# power-vddr.net
KiCad netlist of a schematic drawn in Altium Designer
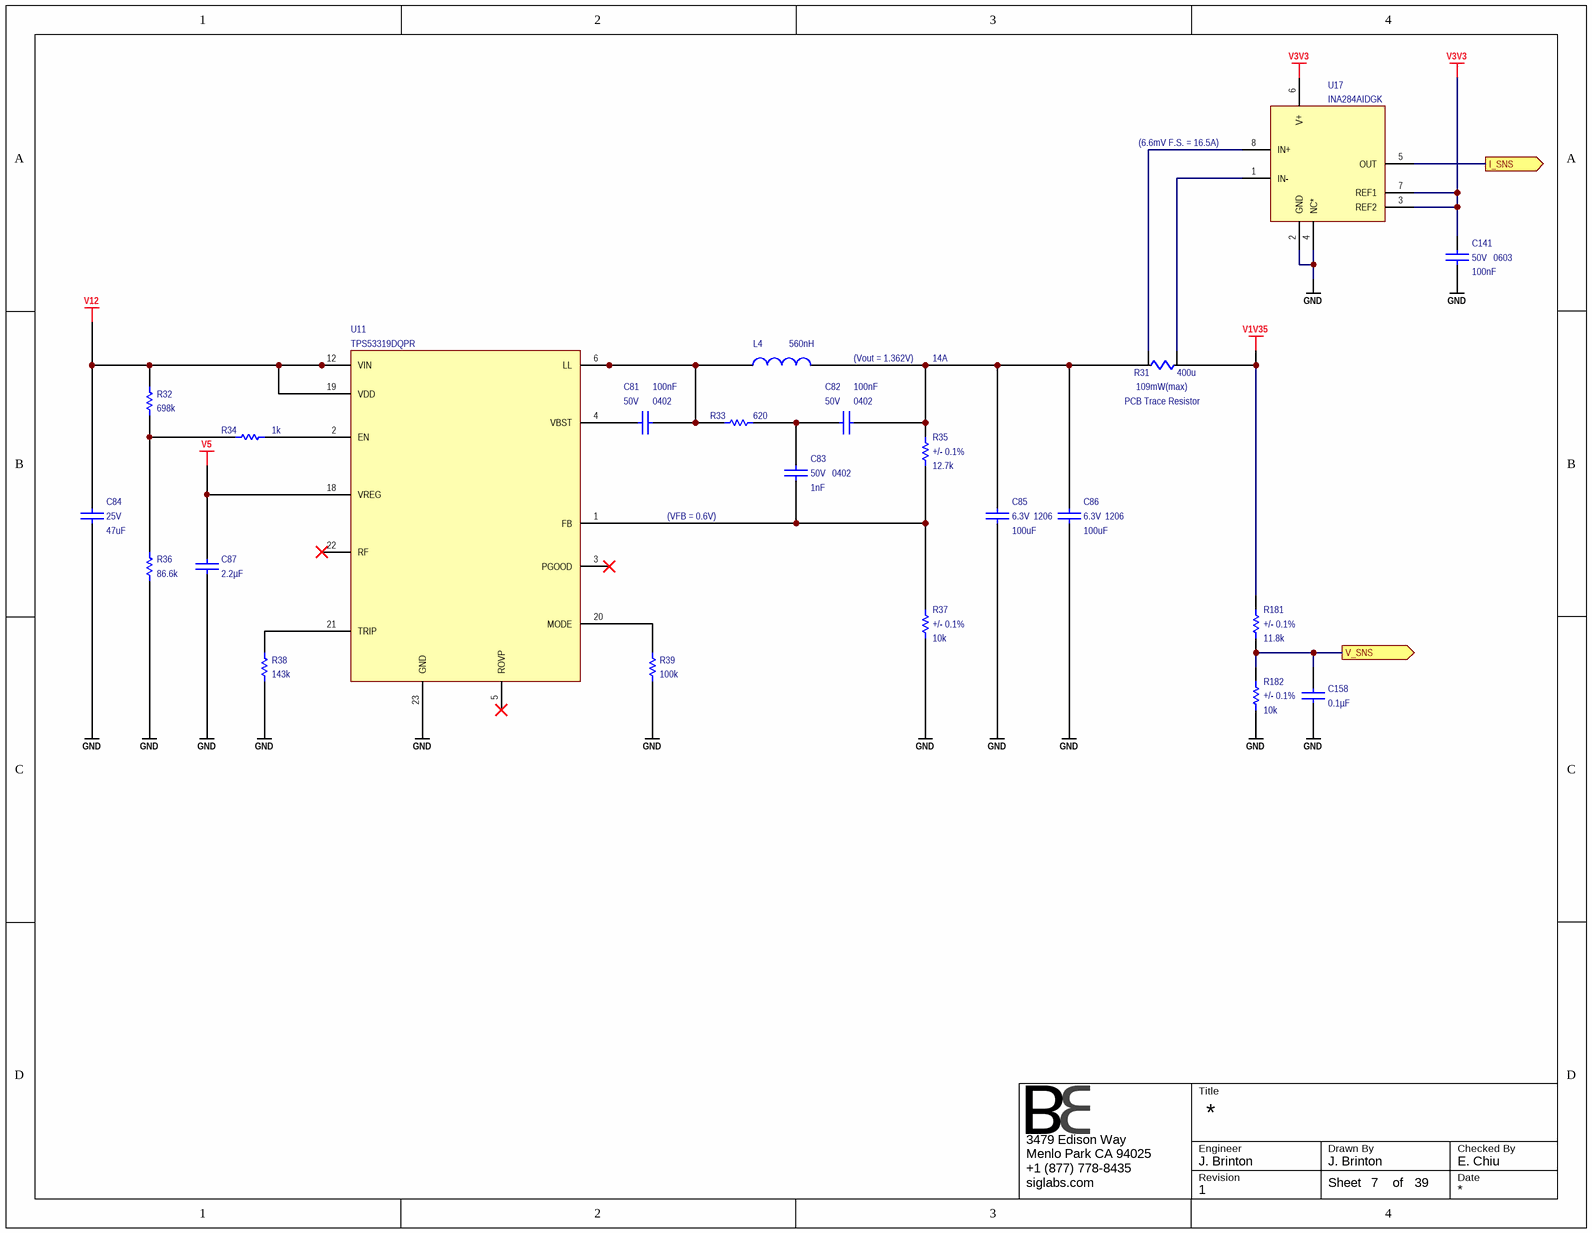
[diagram p0: power-vddr.SchDoc]

(export (version "E")
  (design (tool "Eeschema 10.0.6"))
  (components
    (comp (ref "C81")
      (value "100nF")
      (footprint "CAPC1005X55N")
      (description "Ceramic Capacitor 100nF +/-20% 50V X7R 0402")
      (fields
        (field (name "MANUFACTURER") "Murata Electronics")
        (field (name "VOLTAGE") "50V")
        (field (name "PCB PACKAGE") "0402")
        (field (name "Comment") "GRM155R71H104ME14D")
      )
      (libsource (lib "generic") (part "CAP 0402"))
    )
    (comp (ref "C82")
      (value "100nF")
      (footprint "CAPC1005X55N")
      (description "Ceramic Capacitor 100nF +/-20% 50V X7R 0402")
      (fields
        (field (name "MANUFACTURER") "Murata Electronics")
        (field (name "VOLTAGE") "50V")
        (field (name "PCB PACKAGE") "0402")
        (field (name "Comment") "GRM155R71H104ME14D")
      )
      (libsource (lib "generic") (part "CAP 0402"))
    )
    (comp (ref "C83")
      (value "1nF")
      (footprint "generic:CAPC1005X55N")
      (description "Ceramic Capacitor 1nF +/-10% 50V X7R 0402")
      (fields
        (field (name "MANUFACTURER") "Murata Electronics")
        (field (name "VOLTAGE") "50V")
        (field (name "PCB PACKAGE") "0402")
        (field (name "Comment") "GRM155R71H102KA01J")
      )
      (libsource (lib "generic") (part "CAP"))
    )
    (comp (ref "C84")
      (value "47uF")
      (footprint "tdk:CKG57N")
      (description "Stacked MLCC Capacitor 47uF +/-20% 25V SMD")
      (fields
        (field (name "MANUFACTURER") "TDK Corporation")
        (field (name "TOLERANCE") "+/-20%")
        (field (name "VOLTAGE") "25V")
      )
      (libsource (lib "") (part "CAP_1"))
    )
    (comp (ref "C85")
      (value "100uF")
      (footprint "generic:CAPC3216X180L55N")
      (description "Ceramic Capacitor 100uF +/-20% 6.3V X5R 1206")
      (fields
        (field (name "MANUFACTURER") "Murata Electronics")
        (field (name "VOLTAGE") "6.3V")
        (field (name "PCB PACKAGE") "1206")
        (field (name "Comment") "GRM31CR60J107ME39K")
      )
      (libsource (lib "generic") (part "CAP"))
    )
    (comp (ref "C86")
      (value "100uF")
      (footprint "generic:CAPC3216X180L55N")
      (description "Ceramic Capacitor 100uF +/-20% 6.3V X5R 1206")
      (fields
        (field (name "MANUFACTURER") "Murata Electronics")
        (field (name "VOLTAGE") "6.3V")
        (field (name "PCB PACKAGE") "1206")
        (field (name "Comment") "GRM31CR60J107ME39K")
      )
      (libsource (lib "generic") (part "CAP"))
    )
    (comp (ref "C87")
      (value "2.2µF")
      (footprint "CAPC1608X90N")
      (description "CAP CER 2.2UF 10V 10% X7R 0603")
      (fields (field (name "MANUFACTURER") "Murata Electronics") (field (name "TOLERANCE") "±10%"))
      (libsource (lib "murata") (part "GRM188R71A225KE15D"))
    )
    (comp (ref "C141")
      (value "100nF")
      (footprint "generic:CAPC1608X90N")
      (description "Ceramic Capacitor 100nF +/-10% 50V X7R 0603")
      (fields
        (field (name "MANUFACTURER") "Kemet")
        (field (name "VOLTAGE") "50V")
        (field (name "PCB PACKAGE") "0603")
        (field (name "Comment") "C0603C104K5RACTU")
      )
      (libsource (lib "generic") (part "CAP"))
    )
    (comp (ref "C158")
      (value "0.1µF")
      (footprint "CAPC1005X56N")
      (description "CAP CER 0.1UF 10V 10% X7R 0402")
      (fields (field (name "MANUFACTURER") "Murata Electronics") (field (name "TOLERANCE") "±10%"))
      (libsource (lib "murata") (part "GRM155R71A104KA01J"))
    )
    (comp (ref "L4")
      (value "560nH")
      (footprint "coilcraft:XAL6030")
      (description "Shielded Power Inductor 560nH, 17A")
      (fields (field (name "MANUFACTURER") "Coilcraft") (field (name "Comment") "XAL6030-561MEB"))
      (libsource (lib "generic") (part "INDUCTOR"))
    )
    (comp (ref "R31")
      (value "400u")
      (footprint "RES0.0004")
      (description "Current Sense Resistor 400uOhm TRACE")
      (fields (field (name "Comment") "RES0.0004"))
      (libsource (lib "copper_suicide") (part "RES0.0004"))
    )
    (comp (ref "R32")
      (value "698k")
      (footprint "RESC1005X40N")
      (description "Thick Film Resistor 698k +/-1% 0402")
      (fields (field (name "MANUFACTURER") "Panasonic") (field (name "Comment") "ERJ-2RKF6983X"))
      (libsource (lib "generic") (part "RES 0402"))
    )
    (comp (ref "R33")
      (value "620")
      (footprint "RESC1005X40N")
      (description "Thick Film Resistor 620 +/-5% 0402")
      (fields (field (name "MANUFACTURER") "Panasonic") (field (name "Comment") "ERJ-2GEJ621X"))
      (libsource (lib "generic") (part "RES 0402"))
    )
    (comp (ref "R34")
      (value "1k")
      (footprint "RESC1005X40N")
      (description "Thick Film Resistor 1k +/-1% 0402")
      (fields (field (name "MANUFACTURER") "Panasonic") (field (name "Comment") "ERJ-2RKF1001X"))
      (libsource (lib "generic") (part "RES 0402"))
    )
    (comp (ref "R35")
      (value "12.7k")
      (footprint "RESC2012X70N")
      (description "Thin Film Resistor 12.7k +/-0.1% SMD 0805")
      (fields
        (field (name "TOLERANCE") "+/- 0.1%")
        (field (name "MANUFACTURER") "Susumu")
        (field (name "Comment") "RG2012P-1272-B-T5")
      )
      (libsource (lib "generic") (part "RES"))
    )
    (comp (ref "R36")
      (value "86.6k")
      (footprint "RESC1005X40N")
      (description "Thick Film Resistor 86.6k +/-1% 0402")
      (fields (field (name "MANUFACTURER") "Panasonic") (field (name "Comment") "ERJ-2RKF8662X"))
      (libsource (lib "generic") (part "RES 0402"))
    )
    (comp (ref "R37")
      (value "10k")
      (footprint "RESC2012X70N")
      (description "Thin Film Resistor 10k +/-0.1% SMD 0805")
      (fields
        (field (name "TOLERANCE") "+/- 0.1%")
        (field (name "MANUFACTURER") "Susumu")
        (field (name "Comment") "RG2012P-103-B-T5")
      )
      (libsource (lib "generic") (part "RES"))
    )
    (comp (ref "R38")
      (value "143k")
      (footprint "RESC1005X40N")
      (description "Thick Film Resistor 143k +/-1% 0402")
      (fields (field (name "MANUFACTURER") "Panasonic") (field (name "Comment") "ERJ-2RKF1433X"))
      (libsource (lib "generic") (part "RES 0402"))
    )
    (comp (ref "R39")
      (value "100k")
      (footprint "RESC1005X40N")
      (description "Thick Film Resistor 100k +/-5% 0402")
      (fields (field (name "MANUFACTURER") "Panasonic") (field (name "Comment") "ERJ-2GEJ104X"))
      (libsource (lib "generic") (part "RES 0402"))
    )
    (comp (ref "R181")
      (value "11.8k")
      (footprint "RESC2012X70N")
      (description "Thin Film Resistor 11.8k +/-0.1% SMD 0805")
      (fields
        (field (name "TOLERANCE") "+/- 0.1%")
        (field (name "MANUFACTURER") "Susumu")
        (field (name "Comment") "RG2012P-1182-B-T5")
      )
      (libsource (lib "generic") (part "RES"))
    )
    (comp (ref "R182")
      (value "10k")
      (footprint "RESC2012X70N")
      (description "Thin Film Resistor 10k +/-0.1% SMD 0805")
      (fields
        (field (name "TOLERANCE") "+/- 0.1%")
        (field (name "MANUFACTURER") "Susumu")
        (field (name "Comment") "RG2012P-103-B-T5")
      )
      (libsource (lib "generic") (part "RES"))
    )
    (comp (ref "U11")
      (value "TPS53319DQPR")
      (footprint "texas_instruments:DQP")
      (fields
        (field (name "MANUFACTURER") "Texas Instruments")
        (field (name "MANUFACTURER P/N") "TPS53319DQPR")
      )
      (libsource (lib "ti") (part "TPS53319DQPR"))
    )
    (comp (ref "U17")
      (value "INA284AIDGK")
      (footprint "texas_instruments:S-PDSO-G8")
      (description "Bidirectional Current Shunt Monitor")
      (fields (field (name "MANUFACTURER") "Texas Instruments"))
      (libsource (lib "ti") (part "INA283AIDGK"))
    )
  )
  (nets
    (net (code "1") (name "/I_SNS") (class "Default")
      (node (ref "U17") (pin "5") (pinfunction "OUT_5") (pintype "passive"))
    )
    (net (code "2") (name "/V_SNS") (class "Default")
      (node (ref "C158") (pin "2") (pinfunction "2_2") (pintype "passive"))
      (node (ref "R181") (pin "1") (pinfunction "1_1") (pintype "passive"))
      (node (ref "R182") (pin "2") (pinfunction "2_2") (pintype "passive"))
    )
    (net (code "3") (name "GND") (class "Default")
      (node (ref "C141") (pin "1") (pinfunction "1_1") (pintype "passive"))
      (node (ref "C158") (pin "1") (pinfunction "1_1") (pintype "passive"))
      (node (ref "C84") (pin "1") (pinfunction "1_1") (pintype "passive"))
      (node (ref "C85") (pin "2") (pinfunction "2_2") (pintype "passive"))
      (node (ref "C86") (pin "2") (pinfunction "2_2") (pintype "passive"))
      (node (ref "C87") (pin "1") (pinfunction "1_1") (pintype "passive"))
      (node (ref "R182") (pin "1") (pinfunction "1_1") (pintype "passive"))
      (node (ref "R36") (pin "2") (pinfunction "2_2") (pintype "passive"))
      (node (ref "R37") (pin "1") (pinfunction "1_1") (pintype "passive"))
      (node (ref "R38") (pin "2") (pinfunction "2_2") (pintype "passive"))
      (node (ref "R39") (pin "2") (pinfunction "2_2") (pintype "passive"))
      (node (ref "U11") (pin "23") (pinfunction "GND_23") (pintype "passive"))
      (node (ref "U17") (pin "2") (pinfunction "GND_2") (pintype "passive"))
      (node (ref "U17") (pin "4") (pinfunction "NC*_4") (pintype "passive"))
    )
    (net (code "4") (name "Net-(C81-Pad1)") (class "Default")
      (node (ref "C81") (pin "1") (pinfunction "1_1") (pintype "passive"))
      (node (ref "L4") (pin "1") (pinfunction "1_1") (pintype "passive"))
      (node (ref "R33") (pin "2") (pinfunction "2_2") (pintype "passive"))
      (node (ref "U11") (pin "10") (pinfunction "LL_10") (pintype "passive"))
      (node (ref "U11") (pin "11") (pinfunction "LL_11") (pintype "passive"))
      (node (ref "U11") (pin "6") (pinfunction "LL_6") (pintype "passive"))
      (node (ref "U11") (pin "7") (pinfunction "LL_7") (pintype "passive"))
      (node (ref "U11") (pin "8") (pinfunction "LL_8") (pintype "passive"))
      (node (ref "U11") (pin "9") (pinfunction "LL_9") (pintype "passive"))
    )
    (net (code "5") (name "Net-(C82-Pad1)") (class "Default")
      (node (ref "C82") (pin "1") (pinfunction "1_1") (pintype "passive"))
      (node (ref "C85") (pin "1") (pinfunction "1_1") (pintype "passive"))
      (node (ref "C86") (pin "1") (pinfunction "1_1") (pintype "passive"))
      (node (ref "L4") (pin "2") (pinfunction "2_2") (pintype "passive"))
      (node (ref "R31") (pin "1") (pintype "passive"))
      (node (ref "R35") (pin "2") (pinfunction "2_2") (pintype "passive"))
    )
    (net (code "6") (name "Net-(C82-Pad2)") (class "Default")
      (node (ref "C82") (pin "2") (pinfunction "2_2") (pintype "passive"))
      (node (ref "C83") (pin "1") (pinfunction "1_1") (pintype "passive"))
      (node (ref "R33") (pin "1") (pinfunction "1_1") (pintype "passive"))
    )
    (net (code "7") (name "Net-(R32-Pad2)") (class "Default")
      (node (ref "R32") (pin "2") (pinfunction "2_2") (pintype "passive"))
      (node (ref "R34") (pin "1") (pinfunction "1_1") (pintype "passive"))
      (node (ref "R36") (pin "1") (pinfunction "1_1") (pintype "passive"))
    )
    (net (code "8") (name "Net-(U11-EN)") (class "Default")
      (node (ref "R34") (pin "2") (pinfunction "2_2") (pintype "passive"))
      (node (ref "U11") (pin "2") (pinfunction "EN_2") (pintype "passive"))
    )
    (net (code "9") (name "Net-(U11-FB)") (class "Default")
      (node (ref "C83") (pin "2") (pinfunction "2_2") (pintype "passive"))
      (node (ref "R35") (pin "1") (pinfunction "1_1") (pintype "passive"))
      (node (ref "R37") (pin "2") (pinfunction "2_2") (pintype "passive"))
      (node (ref "U11") (pin "1") (pinfunction "FB_1") (pintype "passive"))
    )
    (net (code "10") (name "Net-(U11-MODE)") (class "Default")
      (node (ref "R39") (pin "1") (pinfunction "1_1") (pintype "passive"))
      (node (ref "U11") (pin "20") (pinfunction "MODE_20") (pintype "passive"))
    )
    (net (code "11") (name "Net-(U11-TRIP)") (class "Default")
      (node (ref "R38") (pin "1") (pinfunction "1_1") (pintype "passive"))
      (node (ref "U11") (pin "21") (pinfunction "TRIP_21") (pintype "passive"))
    )
    (net (code "12") (name "Net-(U11-VBST)") (class "Default")
      (node (ref "C81") (pin "2") (pinfunction "2_2") (pintype "passive"))
      (node (ref "U11") (pin "4") (pinfunction "VBST_4") (pintype "passive"))
    )
    (net (code "13") (name "Net-(U17-IN+)") (class "Default")
      (node (ref "R31") (pin "3") (pintype "passive"))
      (node (ref "U17") (pin "8") (pinfunction "IN+_8") (pintype "passive"))
    )
    (net (code "14") (name "Net-(U17-IN-)") (class "Default")
      (node (ref "R31") (pin "4") (pintype "passive"))
      (node (ref "U17") (pin "1") (pinfunction "IN-_1") (pintype "passive"))
    )
    (net (code "15") (name "V1V35") (class "Default")
      (node (ref "R181") (pin "2") (pinfunction "2_2") (pintype "passive"))
      (node (ref "R31") (pin "2") (pintype "passive"))
    )
    (net (code "16") (name "V3V3") (class "Default")
      (node (ref "C141") (pin "2") (pinfunction "2_2") (pintype "passive"))
      (node (ref "U17") (pin "3") (pinfunction "REF2_3") (pintype "passive"))
      (node (ref "U17") (pin "6") (pinfunction "V+_6") (pintype "passive"))
      (node (ref "U17") (pin "7") (pinfunction "REF1_7") (pintype "passive"))
    )
    (net (code "17") (name "V5") (class "Default")
      (node (ref "C87") (pin "2") (pinfunction "2_2") (pintype "passive"))
      (node (ref "U11") (pin "18") (pinfunction "VREG_18") (pintype "passive"))
    )
    (net (code "18") (name "V12") (class "Default")
      (node (ref "C84") (pin "2") (pinfunction "2_2") (pintype "passive"))
      (node (ref "R32") (pin "1") (pinfunction "1_1") (pintype "passive"))
      (node (ref "U11") (pin "12") (pinfunction "VIN_12") (pintype "passive"))
      (node (ref "U11") (pin "13") (pinfunction "VIN_13") (pintype "passive"))
      (node (ref "U11") (pin "14") (pinfunction "VIN_14") (pintype "passive"))
      (node (ref "U11") (pin "15") (pinfunction "VIN_15") (pintype "passive"))
      (node (ref "U11") (pin "16") (pinfunction "VIN_16") (pintype "passive"))
      (node (ref "U11") (pin "17") (pinfunction "VIN_17") (pintype "passive"))
      (node (ref "U11") (pin "19") (pinfunction "VDD_19") (pintype "passive"))
    )
    (net (code "19") (name "unconnected-(U11-PGOOD-Pad3)") (class "Default")
      (node (ref "U11") (pin "3") (pinfunction "PGOOD_3") (pintype "passive+no_connect"))
    )
    (net (code "20") (name "unconnected-(U11-RF-Pad22)") (class "Default")
      (node (ref "U11") (pin "22") (pinfunction "RF_22") (pintype "passive+no_connect"))
    )
    (net (code "21") (name "unconnected-(U11-ROVP-Pad5)") (class "Default")
      (node (ref "U11") (pin "5") (pinfunction "ROVP_5") (pintype "passive+no_connect"))
    )
  )
)
